# MotorCtrl.net
KiCad netlist of a schematic drawn in Altium Designer
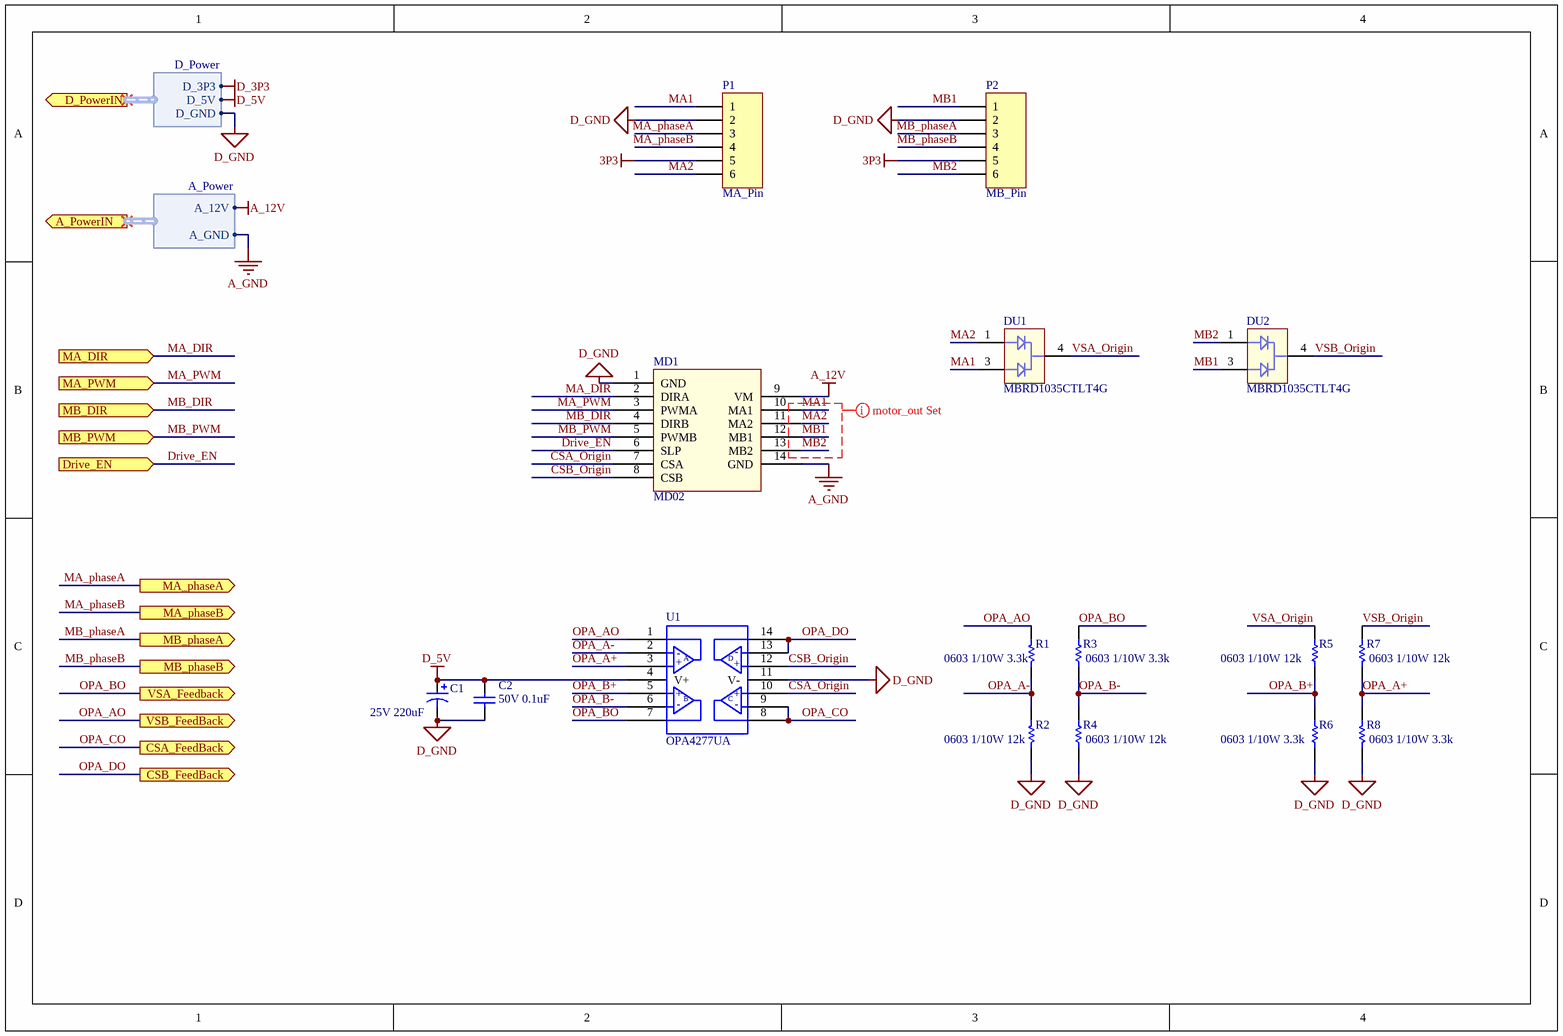
[diagram p0: MotorCtrl.SchDoc]

(export (version "E")
  (design (tool "Eeschema 10.0.6"))
  (components
    (comp (ref "C1")
      (value "25V 220uF")
      (footprint "OWMR:VZT221M1ETR-0607")
      (fields (field (name "PUBLISHER") "Altium Limited"))
      (libsource (lib "Miscellaneous Devices") (part "Cap Pol1"))
    )
    (comp (ref "C2")
      (value "50V 0.1uF")
      (footprint "OWMR:0603F104M500NT")
      (description "50V 100nF Y5V ±20% 0603 Multilayer Ceramic Capacitors MLCC - SMD/SMT ROHS")
      (fields (field (name "PUBLISHER") "Altium Limited"))
      (libsource (lib "Miscellaneous Devices") (part "Cap Semi"))
    )
    (comp (ref "DU1")
      (value "MBRD1035CTLT4G")
      (footprint "OWMR:MBRD1035CTLT4G")
      (description "35V 470mV@5A 5A TO-252-2(DPAK) Schottky Barrier Diodes (SBD) ROHS")
      (libsource (lib "OWMR") (part "MBRD1035CTLT4G"))
    )
    (comp (ref "DU2")
      (value "MBRD1035CTLT4G")
      (footprint "OWMR:MBRD1035CTLT4G")
      (description "35V 470mV@5A 5A TO-252-2(DPAK) Schottky Barrier Diodes (SBD) ROHS")
      (libsource (lib "OWMR") (part "MBRD1035CTLT4G"))
    )
    (comp (ref "MD1")
      (value "MD02")
      (footprint "OWMR:MOTOR_DRIVER")
      (description "17A 2 Cheel Motor Driver")
      (libsource (lib "OWMR") (part "Motor Driver"))
    )
    (comp (ref "P1")
      (value "MA_Pin")
      (footprint "OWMR:S6B-XH-A")
      (description "S6B-XH-A")
      (fields (field (name "PUBLISHER") "Altium Limited"))
      (libsource (lib "Miscellaneous Connectors") (part "Header 6"))
    )
    (comp (ref "P2")
      (value "MB_Pin")
      (footprint "OWMR:S6B-XH-A")
      (description "S6B-XH-A")
      (fields (field (name "PUBLISHER") "Altium Limited"))
      (libsource (lib "Miscellaneous Connectors") (part "Header 6"))
    )
    (comp (ref "R1")
      (value "0603 1/10W 3.3k")
      (footprint "OWMR:0603WAF3301T5E")
      (fields (field (name "PUBLISHER") "Altium Limited"))
      (libsource (lib "Miscellaneous Devices") (part "Res1"))
    )
    (comp (ref "R2")
      (value "0603 1/10W 12k")
      (footprint "OWMR:PTFR0603B12K0N9")
      (fields (field (name "PUBLISHER") "Altium Limited"))
      (libsource (lib "Miscellaneous Devices") (part "Res1"))
    )
    (comp (ref "R3")
      (value "0603 1/10W 3.3k")
      (footprint "OWMR:0603WAF3301T5E")
      (fields (field (name "PUBLISHER") "Altium Limited"))
      (libsource (lib "Miscellaneous Devices") (part "Res1"))
    )
    (comp (ref "R4")
      (value "0603 1/10W 12k")
      (footprint "OWMR:PTFR0603B12K0N9")
      (fields (field (name "PUBLISHER") "Altium Limited"))
      (libsource (lib "Miscellaneous Devices") (part "Res1"))
    )
    (comp (ref "R5")
      (value "0603 1/10W 12k")
      (footprint "OWMR:PTFR0603B12K0N9")
      (fields (field (name "PUBLISHER") "Altium Limited"))
      (libsource (lib "Miscellaneous Devices") (part "Res1"))
    )
    (comp (ref "R6")
      (value "0603 1/10W 3.3k")
      (footprint "OWMR:0603WAF3301T5E")
      (fields (field (name "PUBLISHER") "Altium Limited"))
      (libsource (lib "Miscellaneous Devices") (part "Res1"))
    )
    (comp (ref "R7")
      (value "0603 1/10W 12k")
      (footprint "OWMR:PTFR0603B12K0N9")
      (fields (field (name "PUBLISHER") "Altium Limited"))
      (libsource (lib "Miscellaneous Devices") (part "Res1"))
    )
    (comp (ref "R8")
      (value "0603 1/10W 3.3k")
      (footprint "OWMR:0603WAF3301T5E")
      (fields (field (name "PUBLISHER") "Altium Limited"))
      (libsource (lib "Miscellaneous Devices") (part "Res1"))
    )
    (comp (ref "U1")
      (value "OPA4277UA")
      (footprint "OWMR:OPA4277UA")
      (description "Small Signal Amplifier")
      (libsource (lib "OWMR") (part "Small Signal Amplifier"))
    )
  )
  (nets
    (net (code "3") (name "/CSA_Origin") (class "Default")
      (node (ref "MD1") (pin "7") (pinfunction "CSA_7") (pintype "passive"))
      (node (ref "U1") (pin "10") (pinfunction "+in_C_10") (pintype "passive"))
    )
    (net (code "4") (name "/CSB_Origin") (class "Default")
      (node (ref "MD1") (pin "8") (pinfunction "CSB_8") (pintype "passive"))
      (node (ref "U1") (pin "12") (pinfunction "+In_D_12") (pintype "passive"))
    )
    (net (code "5") (name "/Drive_EN") (class "Default")
      (node (ref "MD1") (pin "6") (pinfunction "SLP_6") (pintype "passive"))
    )
    (net (code "6") (name "/MA1") (class "Default")
      (node (ref "DU1") (pin "3") (pinfunction "3_3") (pintype "passive"))
      (node (ref "MD1") (pin "10") (pinfunction "MA1_10") (pintype "passive"))
      (node (ref "P1") (pin "1") (pinfunction "1_1") (pintype "passive"))
    )
    (net (code "7") (name "/MA2") (class "Default")
      (node (ref "DU1") (pin "1") (pinfunction "1_1") (pintype "passive"))
      (node (ref "MD1") (pin "11") (pinfunction "MA2_11") (pintype "passive"))
      (node (ref "P1") (pin "6") (pinfunction "6_6") (pintype "passive"))
    )
    (net (code "8") (name "/MA_DIR") (class "Default")
      (node (ref "MD1") (pin "2") (pinfunction "DIRA_2") (pintype "passive"))
    )
    (net (code "9") (name "/MA_PWM") (class "Default")
      (node (ref "MD1") (pin "3") (pinfunction "PWMA_3") (pintype "passive"))
    )
    (net (code "10") (name "/MA_phaseA") (class "Default")
      (node (ref "P1") (pin "3") (pinfunction "3_3") (pintype "passive"))
    )
    (net (code "11") (name "/MA_phaseB") (class "Default")
      (node (ref "P1") (pin "4") (pinfunction "4_4") (pintype "passive"))
    )
    (net (code "12") (name "/MB1") (class "Default")
      (node (ref "DU2") (pin "3") (pinfunction "3_3") (pintype "passive"))
      (node (ref "MD1") (pin "12") (pinfunction "MB1_12") (pintype "passive"))
      (node (ref "P2") (pin "1") (pinfunction "1_1") (pintype "passive"))
    )
    (net (code "13") (name "/MB2") (class "Default")
      (node (ref "DU2") (pin "1") (pinfunction "1_1") (pintype "passive"))
      (node (ref "MD1") (pin "13") (pinfunction "MB2_13") (pintype "passive"))
      (node (ref "P2") (pin "6") (pinfunction "6_6") (pintype "passive"))
    )
    (net (code "14") (name "/MB_DIR") (class "Default")
      (node (ref "MD1") (pin "4") (pinfunction "DIRB_4") (pintype "passive"))
    )
    (net (code "15") (name "/MB_PWM") (class "Default")
      (node (ref "MD1") (pin "5") (pinfunction "PWMB_5") (pintype "passive"))
    )
    (net (code "16") (name "/MB_phaseA") (class "Default")
      (node (ref "P2") (pin "3") (pinfunction "3_3") (pintype "passive"))
    )
    (net (code "17") (name "/MB_phaseB") (class "Default")
      (node (ref "P2") (pin "4") (pinfunction "4_4") (pintype "passive"))
    )
    (net (code "18") (name "/OPA_A+") (class "Default")
      (node (ref "R7") (pin "2") (pinfunction "2_2") (pintype "passive"))
      (node (ref "R8") (pin "1") (pinfunction "1_1") (pintype "passive"))
      (node (ref "U1") (pin "3") (pinfunction "+In_A_3") (pintype "passive"))
    )
    (net (code "19") (name "/OPA_A-") (class "Default")
      (node (ref "R1") (pin "1") (pinfunction "1_1") (pintype "passive"))
      (node (ref "R2") (pin "2") (pinfunction "2_2") (pintype "passive"))
      (node (ref "U1") (pin "2") (pinfunction "-In_A_2") (pintype "passive"))
    )
    (net (code "20") (name "/OPA_AO") (class "Default")
      (node (ref "R1") (pin "2") (pinfunction "2_2") (pintype "passive"))
      (node (ref "U1") (pin "1") (pinfunction "Out_A_1") (pintype "passive"))
    )
    (net (code "21") (name "/OPA_B+") (class "Default")
      (node (ref "R5") (pin "2") (pinfunction "2_2") (pintype "passive"))
      (node (ref "R6") (pin "1") (pinfunction "1_1") (pintype "passive"))
      (node (ref "U1") (pin "5") (pinfunction "+In_B_5") (pintype "passive"))
    )
    (net (code "22") (name "/OPA_B-") (class "Default")
      (node (ref "R3") (pin "1") (pinfunction "1_1") (pintype "passive"))
      (node (ref "R4") (pin "2") (pinfunction "2_2") (pintype "passive"))
      (node (ref "U1") (pin "6") (pinfunction "-In_B_6") (pintype "passive"))
    )
    (net (code "23") (name "/OPA_BO") (class "Default")
      (node (ref "R3") (pin "2") (pinfunction "2_2") (pintype "passive"))
      (node (ref "U1") (pin "7") (pinfunction "Out_B_7") (pintype "passive"))
    )
    (net (code "24") (name "/OPA_CO") (class "Default")
      (node (ref "U1") (pin "8") (pinfunction "Out_C_8") (pintype "passive"))
      (node (ref "U1") (pin "9") (pinfunction "-In_C_9") (pintype "passive"))
    )
    (net (code "25") (name "/OPA_DO") (class "Default")
      (node (ref "U1") (pin "13") (pinfunction "-In_D_13") (pintype "passive"))
      (node (ref "U1") (pin "14") (pinfunction "Out_D_14") (pintype "passive"))
    )
    (net (code "26") (name "/VSA_Origin") (class "Default")
      (node (ref "DU1") (pin "4") (pinfunction "4_4") (pintype "passive"))
      (node (ref "R5") (pin "1") (pinfunction "1_1") (pintype "passive"))
    )
    (net (code "27") (name "/VSB_Origin") (class "Default")
      (node (ref "DU2") (pin "4") (pinfunction "4_4") (pintype "passive"))
      (node (ref "R7") (pin "1") (pinfunction "1_1") (pintype "passive"))
    )
    (net (code "30") (name "3P3") (class "Default")
      (node (ref "P1") (pin "5") (pinfunction "5_5") (pintype "passive"))
      (node (ref "P2") (pin "5") (pinfunction "5_5") (pintype "passive"))
    )
    (net (code "31") (name "A_12V") (class "Default")
      (node (ref "MD1") (pin "9") (pinfunction "VM_9") (pintype "passive"))
    )
    (net (code "32") (name "A_GND") (class "Default")
      (node (ref "MD1") (pin "14") (pinfunction "GND_14") (pintype "passive"))
    )
    (net (code "34") (name "D_5V") (class "Default")
      (node (ref "C1") (pin "1") (pinfunction "1_1") (pintype "passive"))
      (node (ref "C2") (pin "2") (pinfunction "2_2") (pintype "passive"))
      (node (ref "U1") (pin "4") (pinfunction "V+_4") (pintype "passive"))
    )
    (net (code "35") (name "D_GND") (class "Default")
      (node (ref "C1") (pin "2") (pinfunction "2_2") (pintype "passive"))
      (node (ref "C2") (pin "1") (pinfunction "1_1") (pintype "passive"))
      (node (ref "MD1") (pin "1") (pinfunction "GND_1") (pintype "passive"))
      (node (ref "P1") (pin "2") (pinfunction "2_2") (pintype "passive"))
      (node (ref "P2") (pin "2") (pinfunction "2_2") (pintype "passive"))
      (node (ref "R2") (pin "1") (pinfunction "1_1") (pintype "passive"))
      (node (ref "R4") (pin "1") (pinfunction "1_1") (pintype "passive"))
      (node (ref "R6") (pin "2") (pinfunction "2_2") (pintype "passive"))
      (node (ref "R8") (pin "2") (pinfunction "2_2") (pintype "passive"))
      (node (ref "U1") (pin "11") (pinfunction "V-_11") (pintype "passive"))
    )
  )
)
